# Soil_moisture.net
KiCad netlist of a schematic drawn in Altium Designer
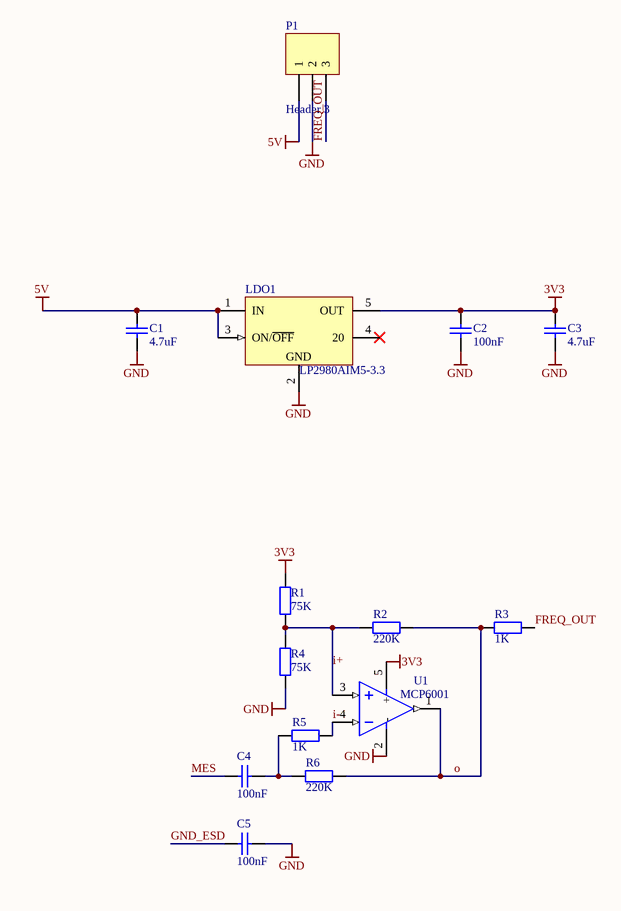
[diagram p0: Soil_moisture.SchDoc]

(export (version "E")
  (design (tool "Eeschema 10.0.6"))
  (components
    (comp (ref "C1")
      (value "4.7uF")
      (footprint "FP_0603_CAP_080")
      (description "Capacitor")
      (libsource (lib "Miscellaneous Devices") (part "Cap"))
    )
    (comp (ref "C2")
      (value "100nF")
      (footprint "FP_0603_CAP_080")
      (description "Capacitor")
      (libsource (lib "Miscellaneous Devices") (part "Cap"))
    )
    (comp (ref "C3")
      (value "4.7uF")
      (footprint "FP_0603_CAP_080")
      (description "Capacitor")
      (libsource (lib "Miscellaneous Devices") (part "Cap"))
    )
    (comp (ref "C4")
      (value "100nF")
      (footprint "FP_0603_CAP_080")
      (description "Capacitor")
      (libsource (lib "Miscellaneous Devices") (part "Cap"))
    )
    (comp (ref "C5")
      (value "100nF")
      (footprint "FP_0603_CAP_080")
      (description "Capacitor")
      (libsource (lib "Miscellaneous Devices") (part "Cap"))
    )
    (comp (ref "LDO1")
      (value "LP2980AIM5-3.3")
      (footprint "SUPPLY_SOT23-5")
      (description "Micropower 50 mA Ultra Low-Dropout Regulator In SOT-23 and micro SMD Packages")
      (libsource (lib "Supply") (part "LP2980IM5-3.8"))
    )
    (comp (ref "P1")
      (value "Header 3")
      (footprint "HDR1X3")
      (description "Header, 3-Pin")
      (fields (field (name "PUBLISHER") "Altium Limited"))
      (libsource (lib "Miscellaneous Connectors") (part "Header 3"))
    )
    (comp (ref "R1")
      (value "75K")
      (footprint "FP_0603_RES")
      (description "Resistor")
      (libsource (lib "") (part "Res3_1"))
    )
    (comp (ref "R2")
      (value "220K")
      (footprint "FP_0603_RES")
      (description "Resistor")
      (libsource (lib "Miscellaneous Devices") (part "Res3"))
    )
    (comp (ref "R3")
      (value "1K")
      (footprint "FP_0603_RES")
      (description "Resistor")
      (libsource (lib "Miscellaneous Devices") (part "Res3"))
    )
    (comp (ref "R4")
      (value "75K")
      (footprint "FP_0603_RES")
      (description "Resistor")
      (libsource (lib "") (part "Res3_1"))
    )
    (comp (ref "R5")
      (value "1K")
      (footprint "FP_0603_RES")
      (description "Resistor")
      (libsource (lib "Miscellaneous Devices") (part "Res3"))
    )
    (comp (ref "R6")
      (value "220K")
      (footprint "FP_0603_RES")
      (description "Resistor")
      (libsource (lib "Miscellaneous Devices") (part "Res3"))
    )
    (comp (ref "U1")
      (value "MCP6001")
      (footprint "ANALOG_SOT23-5")
      (libsource (lib "Analog") (part "MCP6001"))
    )
  )
  (nets
    (net (code "1") (name "/FREQ_OUT") (class "Default")
      (node (ref "P1") (pin "3") (pinfunction "3_3") (pintype "passive"))
      (node (ref "R3") (pin "2") (pinfunction "2_2") (pintype "passive"))
    )
    (net (code "2") (name "/GND_ESD") (class "Default")
      (node (ref "C5") (pin "1") (pinfunction "1_1") (pintype "passive"))
    )
    (net (code "3") (name "/MES") (class "Default")
      (node (ref "C4") (pin "1") (pinfunction "1_1") (pintype "passive"))
    )
    (net (code "4") (name "/i+") (class "Default")
      (node (ref "R1") (pin "2") (pinfunction "2_2") (pintype "passive"))
      (node (ref "R2") (pin "1") (pinfunction "1_1") (pintype "passive"))
      (node (ref "R4") (pin "1") (pinfunction "1_1") (pintype "passive"))
      (node (ref "U1") (pin "3") (pinfunction "IN1+_3") (pintype "input"))
    )
    (net (code "5") (name "/i-") (class "Default")
      (node (ref "R5") (pin "2") (pinfunction "2_2") (pintype "passive"))
      (node (ref "U1") (pin "4") (pinfunction "IN1-_4") (pintype "input"))
    )
    (net (code "6") (name "/o") (class "Default")
      (node (ref "R2") (pin "2") (pinfunction "2_2") (pintype "passive"))
      (node (ref "R3") (pin "1") (pinfunction "1_1") (pintype "passive"))
      (node (ref "R6") (pin "2") (pinfunction "2_2") (pintype "passive"))
      (node (ref "U1") (pin "1") (pinfunction "OUT1_1") (pintype "output"))
    )
    (net (code "7") (name "3V3") (class "Default")
      (node (ref "C2") (pin "2") (pinfunction "2_2") (pintype "passive"))
      (node (ref "C3") (pin "2") (pinfunction "2_2") (pintype "passive"))
      (node (ref "LDO1") (pin "5") (pinfunction "OUT_5") (pintype "passive"))
      (node (ref "R1") (pin "1") (pinfunction "1_1") (pintype "passive"))
      (node (ref "U1") (pin "5") (pinfunction "+_5") (pintype "power_in"))
    )
    (net (code "8") (name "5V") (class "Default")
      (node (ref "C1") (pin "2") (pinfunction "2_2") (pintype "passive"))
      (node (ref "LDO1") (pin "1") (pinfunction "IN_1") (pintype "passive"))
      (node (ref "LDO1") (pin "3") (pinfunction "ON/~{OFF}_3") (pintype "input"))
      (node (ref "P1") (pin "1") (pinfunction "1_1") (pintype "passive"))
    )
    (net (code "9") (name "GND") (class "Default")
      (node (ref "C1") (pin "1") (pinfunction "1_1") (pintype "passive"))
      (node (ref "C2") (pin "1") (pinfunction "1_1") (pintype "passive"))
      (node (ref "C3") (pin "1") (pinfunction "1_1") (pintype "passive"))
      (node (ref "C5") (pin "2") (pinfunction "2_2") (pintype "passive"))
      (node (ref "LDO1") (pin "2") (pinfunction "GND_2") (pintype "passive"))
      (node (ref "P1") (pin "2") (pinfunction "2_2") (pintype "passive"))
      (node (ref "R4") (pin "2") (pinfunction "2_2") (pintype "passive"))
      (node (ref "U1") (pin "2") (pinfunction "-_2") (pintype "power_in"))
    )
    (net (code "10") (name "Net-(C4-Pad2)") (class "Default")
      (node (ref "C4") (pin "2") (pinfunction "2_2") (pintype "passive"))
      (node (ref "R5") (pin "1") (pinfunction "1_1") (pintype "passive"))
      (node (ref "R6") (pin "1") (pinfunction "1_1") (pintype "passive"))
    )
    (net (code "11") (name "unconnected-(LDO1-20-Pad4)") (class "Default")
      (node (ref "LDO1") (pin "4") (pinfunction "20_4") (pintype "passive+no_connect"))
    )
  )
)
